# MSXII-Controller-Breakout.net
KiCad netlist of a schematic drawn in Altium Designer
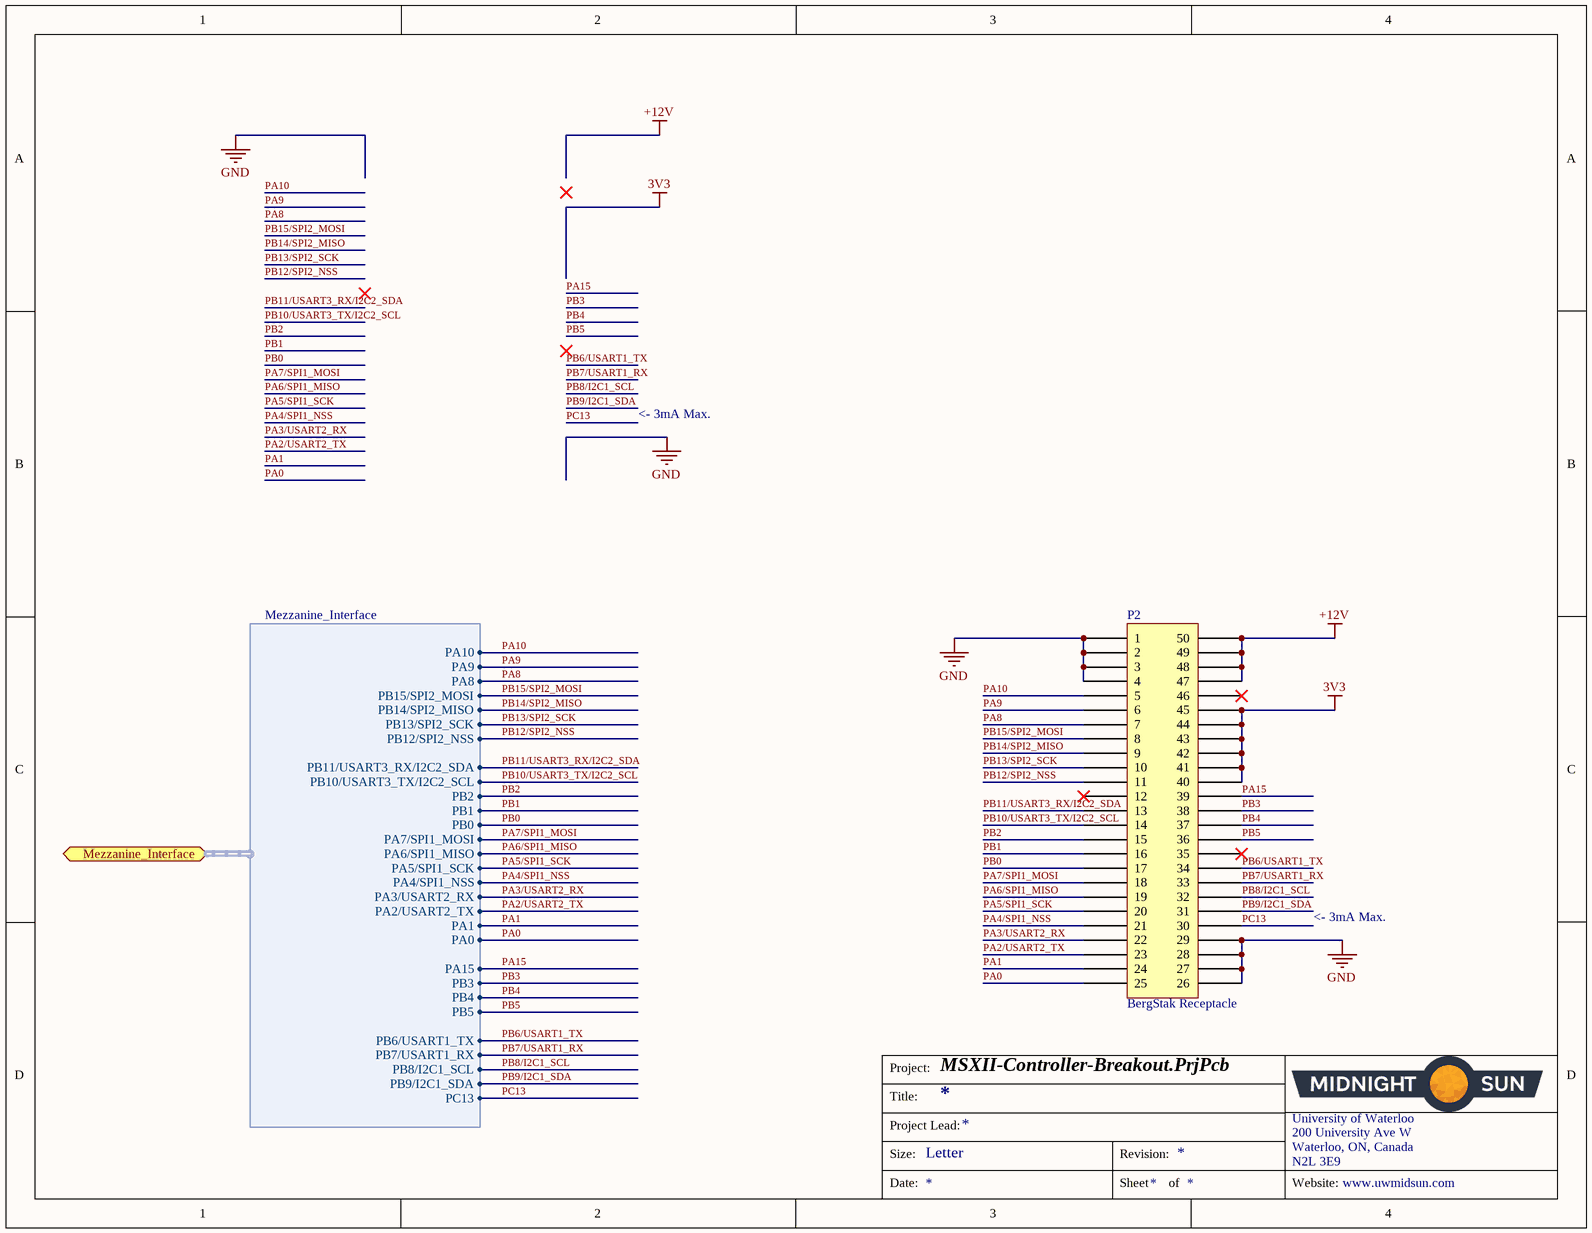
[diagram p0: MSXII-Controller-Breakout.SchDoc]

(export (version "E")
  (design (tool "Eeschema 10.0.6"))
  (components
    (comp (ref "P2")
      (value "BergStak Receptacle")
      (footprint "Bergstak 50 Pos Receptacle")
      (description "50 Position Connector Receptacle, Center Strip Contacts Surface Mount Gold")
      (fields
        (field (name "DIGIKEY PART NUMBER") "609-5227-1-ND")
        (field (name "MANUFACTURER PART NUMBER") "10132798-052100LF")
      )
      (libsource (lib "Midnight Sun Integrated Library") (part "BergStak 50 Position Connector Receptacle"))
    )
  )
  (nets
    (net (code "2") (name "+12V") (class "Default")
      (node (ref "P2") (pin "47") (pinfunction "47_47") (pintype "passive"))
      (node (ref "P2") (pin "48") (pinfunction "48_48") (pintype "passive"))
      (node (ref "P2") (pin "49") (pinfunction "49_49") (pintype "passive"))
      (node (ref "P2") (pin "50") (pinfunction "50_50") (pintype "passive"))
    )
    (net (code "3") (name "/PA0") (class "Default")
      (node (ref "P2") (pin "25") (pinfunction "25_25") (pintype "passive"))
    )
    (net (code "4") (name "/PA1") (class "Default")
      (node (ref "P2") (pin "24") (pinfunction "24_24") (pintype "passive"))
    )
    (net (code "5") (name "/PA2{slash}USART2_TX") (class "Default")
      (node (ref "P2") (pin "23") (pinfunction "23_23") (pintype "passive"))
    )
    (net (code "6") (name "/PA3{slash}USART2_RX") (class "Default")
      (node (ref "P2") (pin "22") (pinfunction "22_22") (pintype "passive"))
    )
    (net (code "7") (name "/PA4{slash}SPI1_NSS") (class "Default")
      (node (ref "P2") (pin "21") (pinfunction "21_21") (pintype "passive"))
    )
    (net (code "8") (name "/PA5{slash}SPI1_SCK") (class "Default")
      (node (ref "P2") (pin "20") (pinfunction "20_20") (pintype "passive"))
    )
    (net (code "9") (name "/PA6{slash}SPI1_MISO") (class "Default")
      (node (ref "P2") (pin "19") (pinfunction "19_19") (pintype "passive"))
    )
    (net (code "10") (name "/PA7{slash}SPI1_MOSI") (class "Default")
      (node (ref "P2") (pin "18") (pinfunction "18_18") (pintype "passive"))
    )
    (net (code "11") (name "/PA8") (class "Default")
      (node (ref "P2") (pin "7") (pinfunction "7_7") (pintype "passive"))
    )
    (net (code "12") (name "/PA9") (class "Default")
      (node (ref "P2") (pin "6") (pinfunction "6_6") (pintype "passive"))
    )
    (net (code "13") (name "/PA10") (class "Default")
      (node (ref "P2") (pin "5") (pinfunction "5_5") (pintype "passive"))
    )
    (net (code "14") (name "/PA15") (class "Default")
      (node (ref "P2") (pin "39") (pinfunction "39_39") (pintype "passive"))
    )
    (net (code "15") (name "/PB0") (class "Default")
      (node (ref "P2") (pin "17") (pinfunction "17_17") (pintype "passive"))
    )
    (net (code "16") (name "/PB1") (class "Default")
      (node (ref "P2") (pin "16") (pinfunction "16_16") (pintype "passive"))
    )
    (net (code "17") (name "/PB2") (class "Default")
      (node (ref "P2") (pin "15") (pinfunction "15_15") (pintype "passive"))
    )
    (net (code "18") (name "/PB3") (class "Default")
      (node (ref "P2") (pin "38") (pinfunction "38_38") (pintype "passive"))
    )
    (net (code "19") (name "/PB4") (class "Default")
      (node (ref "P2") (pin "37") (pinfunction "37_37") (pintype "passive"))
    )
    (net (code "20") (name "/PB5") (class "Default")
      (node (ref "P2") (pin "36") (pinfunction "36_36") (pintype "passive"))
    )
    (net (code "21") (name "/PB6{slash}USART1_TX") (class "Default")
      (node (ref "P2") (pin "34") (pinfunction "34_34") (pintype "passive"))
    )
    (net (code "22") (name "/PB7{slash}USART1_RX") (class "Default")
      (node (ref "P2") (pin "33") (pinfunction "33_33") (pintype "passive"))
    )
    (net (code "23") (name "/PB8{slash}I2C1_SCL") (class "Default")
      (node (ref "P2") (pin "32") (pinfunction "32_32") (pintype "passive"))
    )
    (net (code "24") (name "/PB9{slash}I2C1_SDA") (class "Default")
      (node (ref "P2") (pin "31") (pinfunction "31_31") (pintype "passive"))
    )
    (net (code "25") (name "/PB10{slash}USART3_TX{slash}I2C2_SCL") (class "Default")
      (node (ref "P2") (pin "14") (pinfunction "14_14") (pintype "passive"))
    )
    (net (code "26") (name "/PB11{slash}USART3_RX{slash}I2C2_SDA") (class "Default")
      (node (ref "P2") (pin "13") (pinfunction "13_13") (pintype "passive"))
    )
    (net (code "27") (name "/PB12{slash}SPI2_NSS") (class "Default")
      (node (ref "P2") (pin "11") (pinfunction "11_11") (pintype "passive"))
    )
    (net (code "28") (name "/PB13{slash}SPI2_SCK") (class "Default")
      (node (ref "P2") (pin "10") (pinfunction "10_10") (pintype "passive"))
    )
    (net (code "29") (name "/PB14{slash}SPI2_MISO") (class "Default")
      (node (ref "P2") (pin "9") (pinfunction "9_9") (pintype "passive"))
    )
    (net (code "30") (name "/PB15{slash}SPI2_MOSI") (class "Default")
      (node (ref "P2") (pin "8") (pinfunction "8_8") (pintype "passive"))
    )
    (net (code "31") (name "/PC13") (class "Default")
      (node (ref "P2") (pin "30") (pinfunction "30_30") (pintype "passive"))
    )
    (net (code "33") (name "3V3") (class "Default")
      (node (ref "P2") (pin "40") (pinfunction "40_40") (pintype "passive"))
      (node (ref "P2") (pin "41") (pinfunction "41_41") (pintype "passive"))
      (node (ref "P2") (pin "42") (pinfunction "42_42") (pintype "passive"))
      (node (ref "P2") (pin "43") (pinfunction "43_43") (pintype "passive"))
      (node (ref "P2") (pin "44") (pinfunction "44_44") (pintype "passive"))
      (node (ref "P2") (pin "45") (pinfunction "45_45") (pintype "passive"))
    )
    (net (code "34") (name "GND") (class "Default")
      (node (ref "P2") (pin "1") (pinfunction "1_1") (pintype "passive"))
      (node (ref "P2") (pin "2") (pinfunction "2_2") (pintype "passive"))
      (node (ref "P2") (pin "26") (pinfunction "26_26") (pintype "passive"))
      (node (ref "P2") (pin "27") (pinfunction "27_27") (pintype "passive"))
      (node (ref "P2") (pin "28") (pinfunction "28_28") (pintype "passive"))
      (node (ref "P2") (pin "29") (pinfunction "29_29") (pintype "passive"))
      (node (ref "P2") (pin "3") (pinfunction "3_3") (pintype "passive"))
      (node (ref "P2") (pin "4") (pinfunction "4_4") (pintype "passive"))
    )
    (net (code "35") (name "unconnected-(P2-Pad12)") (class "Default")
      (node (ref "P2") (pin "12") (pinfunction "12_12") (pintype "passive+no_connect"))
    )
    (net (code "36") (name "unconnected-(P2-Pad35)") (class "Default")
      (node (ref "P2") (pin "35") (pinfunction "35_35") (pintype "passive+no_connect"))
    )
    (net (code "37") (name "unconnected-(P2-Pad46)") (class "Default")
      (node (ref "P2") (pin "46") (pinfunction "46_46") (pintype "passive+no_connect"))
    )
  )
)
